# receiver.net
KiCad netlist of a schematic drawn in EAGLE
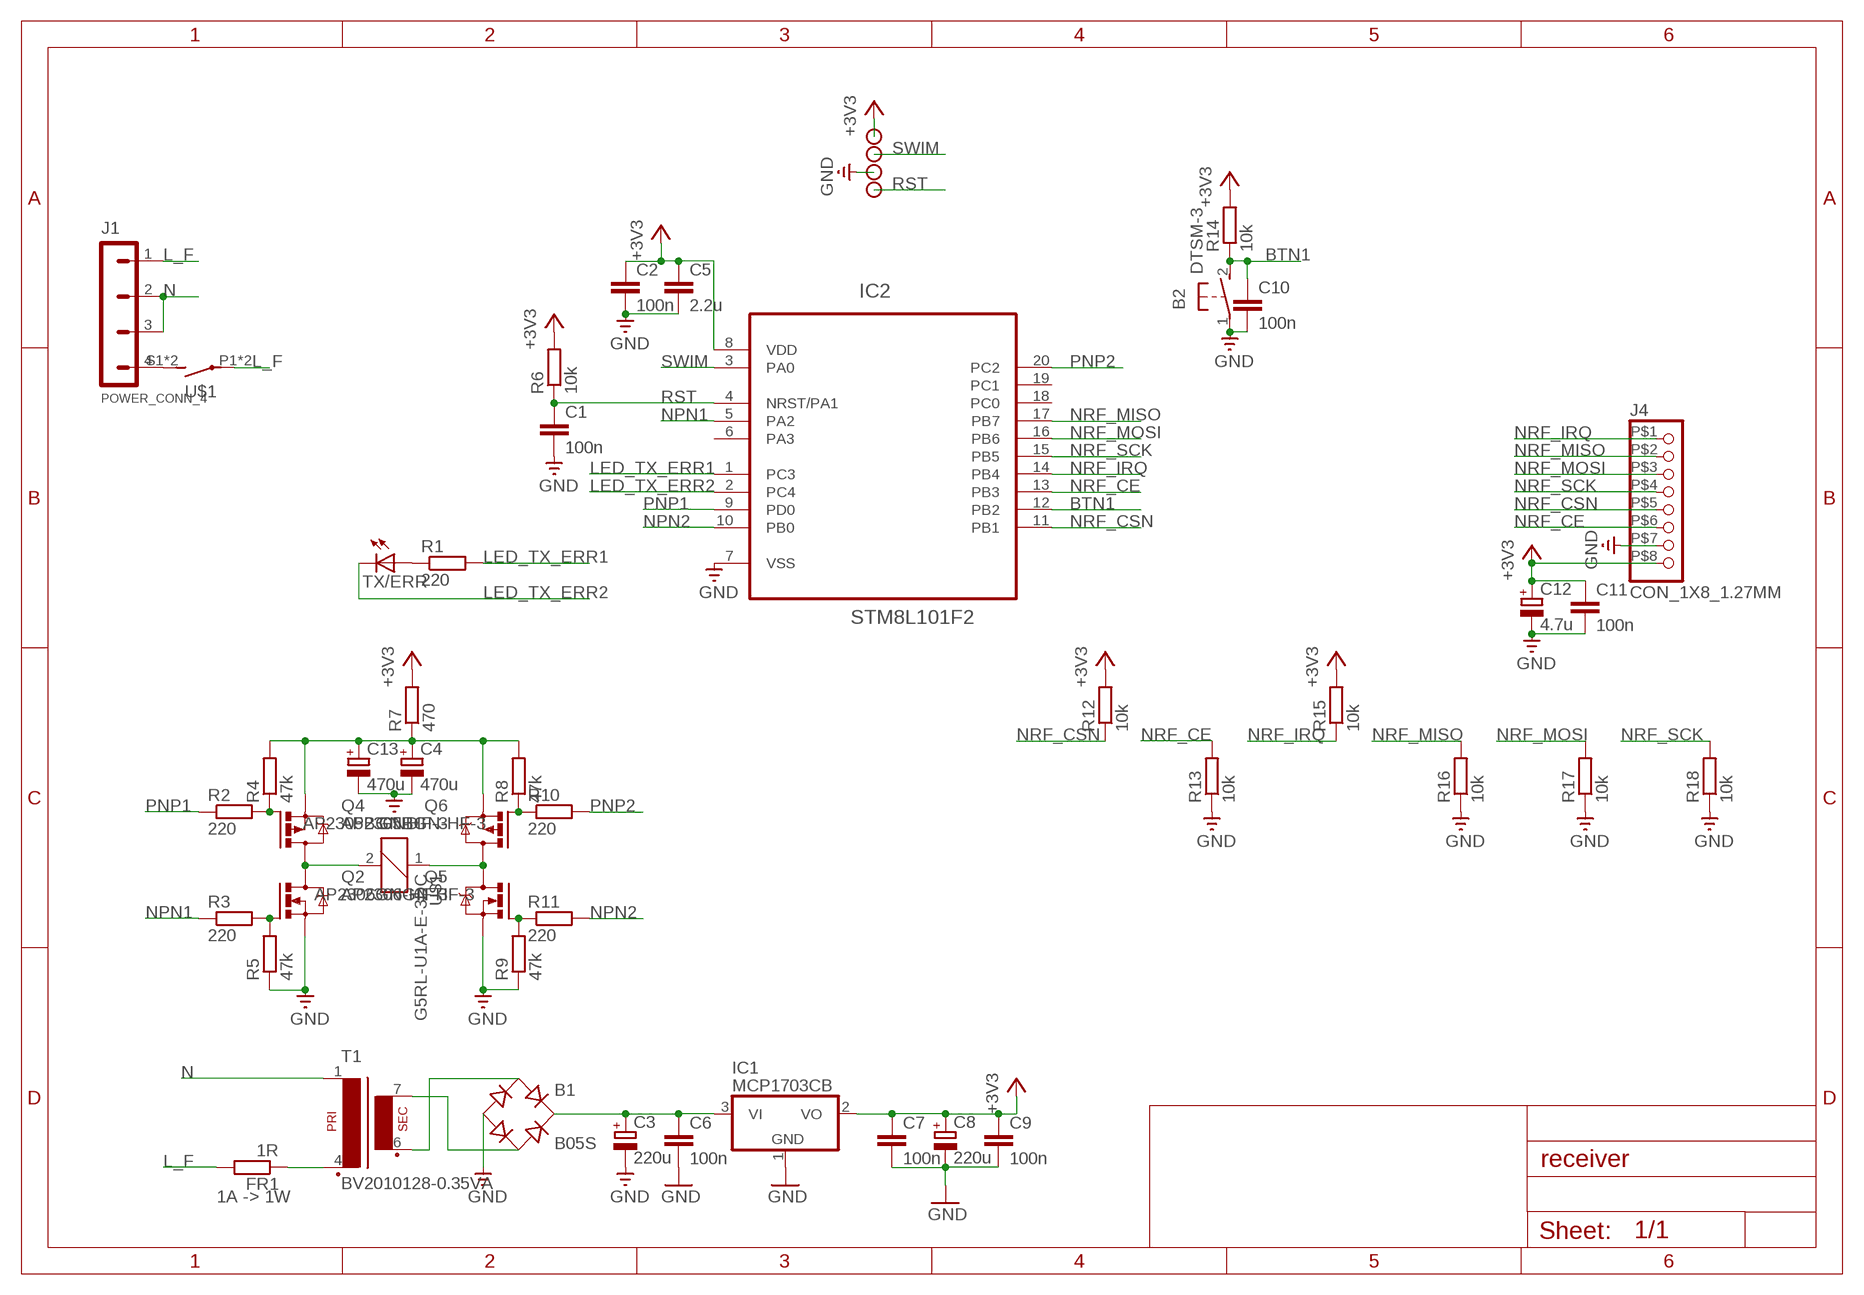
[diagram p0: schematic, sheet 1]

(export (version "E")
  (design (tool "Eeschema 10.0.6"))
  (components
    (comp (ref "B1")
      (value "B05S")
      (footprint "eagle-import:MBS")
      (libsource (lib "eagle-import") (part "BS05"))
    )
    (comp (ref "B2")
      (value "DTSM-3")
      (footprint "eagle-import:DTSM-3")
      (libsource (lib "eagle-import") (part "DTSM-3"))
    )
    (comp (ref "C1")
      (value "100n")
      (footprint "eagle-import:C0603K")
      (libsource (lib "eagle-import") (part "C-EUC0603K"))
    )
    (comp (ref "C2")
      (value "100n")
      (footprint "eagle-import:C0603K")
      (libsource (lib "eagle-import") (part "C-EUC0603K"))
    )
    (comp (ref "C3")
      (value "220u")
      (footprint "eagle-import:E3,5-8")
      (libsource (lib "eagle-import") (part "CPOL-EUE3.5-8"))
    )
    (comp (ref "C4")
      (value "470u")
      (footprint "eagle-import:E2,5-6")
      (libsource (lib "eagle-import") (part "CPOL-EUE2.5-6"))
    )
    (comp (ref "C5")
      (value "2.2u")
      (footprint "eagle-import:C0805K")
      (libsource (lib "eagle-import") (part "C-EUC0805K"))
    )
    (comp (ref "C6")
      (value "100n")
      (footprint "eagle-import:C0603K")
      (libsource (lib "eagle-import") (part "C-EUC0603K"))
    )
    (comp (ref "C7")
      (value "100n")
      (footprint "eagle-import:C0603K")
      (libsource (lib "eagle-import") (part "C-EUC0603K"))
    )
    (comp (ref "C8")
      (value "220u")
      (footprint "eagle-import:E2,5-6")
      (libsource (lib "eagle-import") (part "CPOL-EUE2.5-6"))
    )
    (comp (ref "C9")
      (value "100n")
      (footprint "eagle-import:C0603K")
      (libsource (lib "eagle-import") (part "C-EUC0603K"))
    )
    (comp (ref "C10")
      (value "100n")
      (footprint "eagle-import:C0603K")
      (libsource (lib "eagle-import") (part "C-EUC0603K"))
    )
    (comp (ref "C11")
      (value "100n")
      (footprint "eagle-import:C0603K")
      (libsource (lib "eagle-import") (part "C-EUC0603K"))
    )
    (comp (ref "C12")
      (value "4.7u")
      (footprint "eagle-import:SMC_A")
      (libsource (lib "eagle-import") (part "CPOL-EUSMCA"))
    )
    (comp (ref "C13")
      (value "470u")
      (footprint "eagle-import:E2,5-6")
      (libsource (lib "eagle-import") (part "CPOL-EUE2.5-6"))
    )
    (comp (ref "FR1")
      (value "1R")
      (footprint "eagle-import:0309_10")
      (libsource (lib "eagle-import") (part "R-EU_0309/10"))
    )
    (comp (ref "IC1")
      (value "MCP1703CB")
      (footprint "eagle-import:SOT23")
      (libsource (lib "eagle-import") (part "MCP1703CB"))
    )
    (comp (ref "IC2")
      (value "STM8L101F2")
      (footprint "eagle-import:TSSOP20")
      (libsource (lib "eagle-import") (part "STM8L101F2"))
    )
    (comp (ref "J1")
      (value "POWER_CONN_4")
      (footprint "eagle-import:TERMINAL_BLOCK_4")
      (libsource (lib "eagle-import") (part "POWER_CONN_4"))
    )
    (comp (ref "J4")
      (value "CON_1X8_1.27MM")
      (footprint "eagle-import:CON_1X8PIN_1.27MM")
      (libsource (lib "eagle-import") (part "CON_1X8_1.27MM"))
    )
    (comp (ref "Q2")
      (value "AP2306GN-HF-3")
      (footprint "eagle-import:SOT23")
      (libsource (lib "eagle-import") (part "AP2306GN-HF-3"))
    )
    (comp (ref "Q4")
      (value "AP2305BGN-HF-3")
      (footprint "eagle-import:SOT23")
      (libsource (lib "eagle-import") (part "AP2305BGN-HF-3"))
    )
    (comp (ref "Q5")
      (value "AP2306GN-HF-3")
      (footprint "eagle-import:SOT23")
      (libsource (lib "eagle-import") (part "AP2306GN-HF-3"))
    )
    (comp (ref "Q6")
      (value "AP2305BGN-HF-3")
      (footprint "eagle-import:SOT23")
      (libsource (lib "eagle-import") (part "AP2305BGN-HF-3"))
    )
    (comp (ref "R1")
      (value "220")
      (footprint "eagle-import:R0603")
      (libsource (lib "eagle-import") (part "R-EU_R0603"))
    )
    (comp (ref "R2")
      (value "220")
      (footprint "eagle-import:R0603")
      (libsource (lib "eagle-import") (part "R-EU_R0603"))
    )
    (comp (ref "R3")
      (value "220")
      (footprint "eagle-import:R0603")
      (libsource (lib "eagle-import") (part "R-EU_R0603"))
    )
    (comp (ref "R4")
      (value "47k")
      (footprint "eagle-import:R0603")
      (libsource (lib "eagle-import") (part "R-EU_R0603"))
    )
    (comp (ref "R5")
      (value "47k")
      (footprint "eagle-import:R0603")
      (libsource (lib "eagle-import") (part "R-EU_R0603"))
    )
    (comp (ref "R6")
      (value "10k")
      (footprint "eagle-import:R0603")
      (libsource (lib "eagle-import") (part "R-EU_R0603"))
    )
    (comp (ref "R7")
      (value "470")
      (footprint "eagle-import:R0603")
      (libsource (lib "eagle-import") (part "R-EU_R0603"))
    )
    (comp (ref "R8")
      (value "47k")
      (footprint "eagle-import:R0603")
      (libsource (lib "eagle-import") (part "R-EU_R0603"))
    )
    (comp (ref "R9")
      (value "47k")
      (footprint "eagle-import:R0603")
      (libsource (lib "eagle-import") (part "R-EU_R0603"))
    )
    (comp (ref "R10")
      (value "220")
      (footprint "eagle-import:R0603")
      (libsource (lib "eagle-import") (part "R-EU_R0603"))
    )
    (comp (ref "R11")
      (value "220")
      (footprint "eagle-import:R0603")
      (libsource (lib "eagle-import") (part "R-EU_R0603"))
    )
    (comp (ref "R12")
      (value "10k")
      (footprint "eagle-import:R0603")
      (libsource (lib "eagle-import") (part "R-EU_R0603"))
    )
    (comp (ref "R13")
      (value "10k")
      (footprint "eagle-import:R0603")
      (libsource (lib "eagle-import") (part "R-EU_R0603"))
    )
    (comp (ref "R14")
      (value "10k")
      (footprint "eagle-import:R0603")
      (libsource (lib "eagle-import") (part "R-EU_R0603"))
    )
    (comp (ref "R15")
      (value "10k")
      (footprint "eagle-import:R0603")
      (libsource (lib "eagle-import") (part "R-EU_R0603"))
    )
    (comp (ref "R16")
      (value "10k")
      (footprint "eagle-import:R0603")
      (libsource (lib "eagle-import") (part "R-EU_R0603"))
    )
    (comp (ref "R17")
      (value "10k")
      (footprint "eagle-import:R0603")
      (libsource (lib "eagle-import") (part "R-EU_R0603"))
    )
    (comp (ref "R18")
      (value "10k")
      (footprint "eagle-import:R0603")
      (libsource (lib "eagle-import") (part "R-EU_R0603"))
    )
    (comp (ref "SIG_+3V1")
      (value "CON_PAD")
      (footprint "eagle-import:SMD_PAD")
      (libsource (lib "eagle-import") (part "CON_PAD"))
    )
    (comp (ref "SIG_GND")
      (value "CON_PAD")
      (footprint "eagle-import:SMD_PAD")
      (libsource (lib "eagle-import") (part "CON_PAD"))
    )
    (comp (ref "SIG_RST")
      (value "CON_PAD")
      (footprint "eagle-import:SMD_PAD")
      (libsource (lib "eagle-import") (part "CON_PAD"))
    )
    (comp (ref "SIG_SWIM")
      (value "CON_PAD")
      (footprint "eagle-import:SMD_PAD")
      (libsource (lib "eagle-import") (part "CON_PAD"))
    )
    (comp (ref "T1")
      (value "BV2010128-0.35VA")
      (footprint "eagle-import:BV2010128-0.35VA")
      (libsource (lib "eagle-import") (part "BV2010128-0.35VA"))
    )
    (comp (ref "TX/ERR")
      (value "LED3MM")
      (footprint "eagle-import:LED3MM")
      (libsource (lib "eagle-import") (part "LED3MM"))
    )
    (comp (ref "U$1")
      (value "G5RL-U1A-E-3DC")
      (footprint "eagle-import:G5RL-U1A-E-3DC")
      (libsource (lib "eagle-import") (part "G5RL-U1A-E-3DC"))
    )
  )
  (nets
    (net (code "1") (name "+3V3") (class "Default")
      (node (ref "C11") (pin "1") (pinfunction "1_1") (pintype "passive"))
      (node (ref "C12") (pin "+") (pinfunction "+_+") (pintype "passive"))
      (node (ref "C2") (pin "1") (pinfunction "1_1") (pintype "passive"))
      (node (ref "C5") (pin "1") (pinfunction "1_1") (pintype "passive"))
      (node (ref "C7") (pin "1") (pinfunction "1_1") (pintype "passive"))
      (node (ref "C8") (pin "+") (pinfunction "+_+") (pintype "passive"))
      (node (ref "C9") (pin "1") (pinfunction "1_1") (pintype "passive"))
      (node (ref "IC1") (pin "2") (pinfunction "VO_2") (pintype "passive"))
      (node (ref "IC2") (pin "8") (pinfunction "VDD_8") (pintype "power_in"))
      (node (ref "J4") (pin "P$8") (pinfunction "8_P$8") (pintype "passive"))
      (node (ref "R12") (pin "2") (pinfunction "2_2") (pintype "passive"))
      (node (ref "R14") (pin "2") (pinfunction "2_2") (pintype "passive"))
      (node (ref "R15") (pin "2") (pinfunction "2_2") (pintype "passive"))
      (node (ref "R6") (pin "2") (pinfunction "2_2") (pintype "passive"))
      (node (ref "R7") (pin "2") (pinfunction "2_2") (pintype "passive"))
      (node (ref "SIG_+3V1") (pin "P$1") (pinfunction "P$1_P$1") (pintype "bidirectional"))
    )
    (net (code "2") (name "/BTN1") (class "Default")
      (node (ref "B2") (pin "2") (pinfunction "2_2") (pintype "passive"))
      (node (ref "C10") (pin "1") (pinfunction "1_1") (pintype "passive"))
      (node (ref "IC2") (pin "12") (pinfunction "PB2_12") (pintype "bidirectional"))
      (node (ref "R14") (pin "1") (pinfunction "1_1") (pintype "passive"))
    )
    (net (code "3") (name "/LED_TX_ERR1") (class "Default")
      (node (ref "IC2") (pin "1") (pinfunction "PC3_1") (pintype "bidirectional"))
      (node (ref "R1") (pin "2") (pinfunction "2_2") (pintype "passive"))
    )
    (net (code "4") (name "/LED_TX_ERR2") (class "Default")
      (node (ref "IC2") (pin "2") (pinfunction "PC4_2") (pintype "bidirectional"))
      (node (ref "TX/ERR") (pin "K") (pinfunction "C_K") (pintype "passive"))
    )
    (net (code "5") (name "/L_F") (class "Default")
      (node (ref "FR1") (pin "2") (pinfunction "2_2") (pintype "passive"))
      (node (ref "J1") (pin "1") (pinfunction "P$1_1") (pintype "bidirectional"))
      (node (ref "U$1") (pin "P1") (pinfunction "P_P1") (pintype "passive"))
      (node (ref "U$1") (pin "P2") (pinfunction "P_P2") (pintype "passive"))
    )
    (net (code "6") (name "/N") (class "Default")
      (node (ref "J1") (pin "2") (pinfunction "P$2_2") (pintype "bidirectional"))
      (node (ref "J1") (pin "3") (pinfunction "P$3_3") (pintype "bidirectional"))
      (node (ref "T1") (pin "1") (pinfunction "P1_1") (pintype "passive"))
    )
    (net (code "7") (name "/NPN1") (class "Default")
      (node (ref "IC2") (pin "5") (pinfunction "PA2_5") (pintype "bidirectional"))
      (node (ref "R3") (pin "1") (pinfunction "1_1") (pintype "passive"))
    )
    (net (code "8") (name "/NPN2") (class "Default")
      (node (ref "IC2") (pin "10") (pinfunction "PB0_10") (pintype "bidirectional"))
      (node (ref "R11") (pin "2") (pinfunction "2_2") (pintype "passive"))
    )
    (net (code "9") (name "/NRF_CE") (class "Default")
      (node (ref "IC2") (pin "13") (pinfunction "PB3_13") (pintype "bidirectional"))
      (node (ref "J4") (pin "P$6") (pinfunction "6_P$6") (pintype "passive"))
      (node (ref "R13") (pin "2") (pinfunction "2_2") (pintype "passive"))
    )
    (net (code "10") (name "/NRF_CSN") (class "Default")
      (node (ref "IC2") (pin "11") (pinfunction "PB1_11") (pintype "bidirectional"))
      (node (ref "J4") (pin "P$5") (pinfunction "5_P$5") (pintype "passive"))
      (node (ref "R12") (pin "1") (pinfunction "1_1") (pintype "passive"))
    )
    (net (code "11") (name "/NRF_IRQ") (class "Default")
      (node (ref "IC2") (pin "14") (pinfunction "PB4_14") (pintype "bidirectional"))
      (node (ref "J4") (pin "P$1") (pinfunction "1_P$1") (pintype "passive"))
      (node (ref "R15") (pin "1") (pinfunction "1_1") (pintype "passive"))
    )
    (net (code "12") (name "/NRF_MISO") (class "Default")
      (node (ref "IC2") (pin "17") (pinfunction "PB7_17") (pintype "bidirectional"))
      (node (ref "J4") (pin "P$2") (pinfunction "2_P$2") (pintype "passive"))
      (node (ref "R16") (pin "2") (pinfunction "2_2") (pintype "passive"))
    )
    (net (code "13") (name "/NRF_MOSI") (class "Default")
      (node (ref "IC2") (pin "16") (pinfunction "PB6_16") (pintype "bidirectional"))
      (node (ref "J4") (pin "P$3") (pinfunction "3_P$3") (pintype "passive"))
      (node (ref "R17") (pin "2") (pinfunction "2_2") (pintype "passive"))
    )
    (net (code "14") (name "/NRF_SCK") (class "Default")
      (node (ref "IC2") (pin "15") (pinfunction "PB5_15") (pintype "bidirectional"))
      (node (ref "J4") (pin "P$4") (pinfunction "4_P$4") (pintype "passive"))
      (node (ref "R18") (pin "2") (pinfunction "2_2") (pintype "passive"))
    )
    (net (code "15") (name "/PNP1") (class "Default")
      (node (ref "IC2") (pin "9") (pinfunction "PD0_9") (pintype "bidirectional"))
      (node (ref "R2") (pin "1") (pinfunction "1_1") (pintype "passive"))
    )
    (net (code "16") (name "/PNP2") (class "Default")
      (node (ref "IC2") (pin "20") (pinfunction "PC2_20") (pintype "bidirectional"))
      (node (ref "R10") (pin "2") (pinfunction "2_2") (pintype "passive"))
    )
    (net (code "17") (name "/RST") (class "Default")
      (node (ref "C1") (pin "1") (pinfunction "1_1") (pintype "passive"))
      (node (ref "IC2") (pin "4") (pinfunction "NRST/PA1_4") (pintype "bidirectional"))
      (node (ref "R6") (pin "1") (pinfunction "1_1") (pintype "passive"))
      (node (ref "SIG_RST") (pin "P$1") (pinfunction "P$1_P$1") (pintype "bidirectional"))
    )
    (net (code "18") (name "/SWIM") (class "Default")
      (node (ref "IC2") (pin "3") (pinfunction "PA0_3") (pintype "power_in"))
      (node (ref "SIG_SWIM") (pin "P$1") (pinfunction "P$1_P$1") (pintype "bidirectional"))
    )
    (net (code "19") (name "GND") (class "Default")
      (node (ref "B1") (pin "-") (pinfunction "-_-") (pintype "passive"))
      (node (ref "B2") (pin "1") (pinfunction "1_1") (pintype "passive"))
      (node (ref "C1") (pin "2") (pinfunction "2_2") (pintype "passive"))
      (node (ref "C10") (pin "2") (pinfunction "2_2") (pintype "passive"))
      (node (ref "C11") (pin "2") (pinfunction "2_2") (pintype "passive"))
      (node (ref "C12") (pin "-") (pinfunction "-_-") (pintype "passive"))
      (node (ref "C13") (pin "-") (pinfunction "-_-") (pintype "passive"))
      (node (ref "C2") (pin "2") (pinfunction "2_2") (pintype "passive"))
      (node (ref "C3") (pin "-") (pinfunction "-_-") (pintype "passive"))
      (node (ref "C4") (pin "-") (pinfunction "-_-") (pintype "passive"))
      (node (ref "C5") (pin "2") (pinfunction "2_2") (pintype "passive"))
      (node (ref "C6") (pin "2") (pinfunction "2_2") (pintype "passive"))
      (node (ref "C7") (pin "2") (pinfunction "2_2") (pintype "passive"))
      (node (ref "C8") (pin "-") (pinfunction "-_-") (pintype "passive"))
      (node (ref "C9") (pin "2") (pinfunction "2_2") (pintype "passive"))
      (node (ref "IC1") (pin "1") (pinfunction "GND_1") (pintype "passive"))
      (node (ref "IC2") (pin "7") (pinfunction "VSS_7") (pintype "power_in"))
      (node (ref "J4") (pin "P$7") (pinfunction "7_P$7") (pintype "passive"))
      (node (ref "Q2") (pin "2") (pinfunction "S_2") (pintype "passive"))
      (node (ref "Q5") (pin "2") (pinfunction "S_2") (pintype "passive"))
      (node (ref "R13") (pin "1") (pinfunction "1_1") (pintype "passive"))
      (node (ref "R16") (pin "1") (pinfunction "1_1") (pintype "passive"))
      (node (ref "R17") (pin "1") (pinfunction "1_1") (pintype "passive"))
      (node (ref "R18") (pin "1") (pinfunction "1_1") (pintype "passive"))
      (node (ref "R5") (pin "1") (pinfunction "1_1") (pintype "passive"))
      (node (ref "R9") (pin "1") (pinfunction "1_1") (pintype "passive"))
      (node (ref "SIG_GND") (pin "P$1") (pinfunction "P$1_P$1") (pintype "bidirectional"))
    )
    (net (code "20") (name "Net-(IC1-VI)") (class "Default")
      (node (ref "B1") (pin "+") (pinfunction "+_+") (pintype "passive"))
      (node (ref "C3") (pin "+") (pinfunction "+_+") (pintype "passive"))
      (node (ref "C6") (pin "1") (pinfunction "1_1") (pintype "passive"))
      (node (ref "IC1") (pin "3") (pinfunction "VI_3") (pintype "input"))
    )
    (net (code "21") (name "Net-(J1-P$4)") (class "Default")
      (node (ref "J1") (pin "4") (pinfunction "P$4_4") (pintype "bidirectional"))
      (node (ref "U$1") (pin "S1") (pinfunction "S_S1") (pintype "passive"))
      (node (ref "U$1") (pin "S2") (pinfunction "S_S2") (pintype "passive"))
    )
    (net (code "22") (name "Net-(Q2-D)") (class "Default")
      (node (ref "Q2") (pin "3") (pinfunction "D_3") (pintype "passive"))
      (node (ref "Q4") (pin "3") (pinfunction "D_3") (pintype "passive"))
      (node (ref "U$1") (pin "2") (pinfunction "2_2") (pintype "passive"))
    )
    (net (code "23") (name "Net-(Q2-G)") (class "Default")
      (node (ref "Q2") (pin "1") (pinfunction "G_1") (pintype "passive"))
      (node (ref "R3") (pin "2") (pinfunction "2_2") (pintype "passive"))
      (node (ref "R5") (pin "2") (pinfunction "2_2") (pintype "passive"))
    )
    (net (code "24") (name "Net-(Q4-G)") (class "Default")
      (node (ref "Q4") (pin "1") (pinfunction "G_1") (pintype "passive"))
      (node (ref "R2") (pin "2") (pinfunction "2_2") (pintype "passive"))
      (node (ref "R4") (pin "1") (pinfunction "1_1") (pintype "passive"))
    )
    (net (code "25") (name "Net-(Q4-S)") (class "Default")
      (node (ref "C13") (pin "+") (pinfunction "+_+") (pintype "passive"))
      (node (ref "C4") (pin "+") (pinfunction "+_+") (pintype "passive"))
      (node (ref "Q4") (pin "2") (pinfunction "S_2") (pintype "passive"))
      (node (ref "Q6") (pin "2") (pinfunction "S_2") (pintype "passive"))
      (node (ref "R4") (pin "2") (pinfunction "2_2") (pintype "passive"))
      (node (ref "R7") (pin "1") (pinfunction "1_1") (pintype "passive"))
      (node (ref "R8") (pin "2") (pinfunction "2_2") (pintype "passive"))
    )
    (net (code "26") (name "Net-(Q5-D)") (class "Default")
      (node (ref "Q5") (pin "3") (pinfunction "D_3") (pintype "passive"))
      (node (ref "Q6") (pin "3") (pinfunction "D_3") (pintype "passive"))
      (node (ref "U$1") (pin "1") (pinfunction "1_1") (pintype "passive"))
    )
    (net (code "27") (name "Net-(Q5-G)") (class "Default")
      (node (ref "Q5") (pin "1") (pinfunction "G_1") (pintype "passive"))
      (node (ref "R11") (pin "1") (pinfunction "1_1") (pintype "passive"))
      (node (ref "R9") (pin "2") (pinfunction "2_2") (pintype "passive"))
    )
    (net (code "28") (name "Net-(Q6-G)") (class "Default")
      (node (ref "Q6") (pin "1") (pinfunction "G_1") (pintype "passive"))
      (node (ref "R10") (pin "1") (pinfunction "1_1") (pintype "passive"))
      (node (ref "R8") (pin "1") (pinfunction "1_1") (pintype "passive"))
    )
    (net (code "29") (name "Net-(R1-Pad1)") (class "Default")
      (node (ref "R1") (pin "1") (pinfunction "1_1") (pintype "passive"))
      (node (ref "TX/ERR") (pin "A") (pinfunction "A_A") (pintype "passive"))
    )
    (net (code "30") (name "Net-(T1-P2)") (class "Default")
      (node (ref "FR1") (pin "1") (pinfunction "1_1") (pintype "passive"))
      (node (ref "T1") (pin "4") (pinfunction "P2_4") (pintype "passive"))
    )
    (net (code "31") (name "Net-(T1-S3)") (class "Default")
      (node (ref "B1") (pin "AC1") (pinfunction "AC1_AC1") (pintype "passive"))
      (node (ref "T1") (pin "6") (pinfunction "S3_6") (pintype "passive"))
    )
    (net (code "32") (name "Net-(T1-S4)") (class "Default")
      (node (ref "B1") (pin "AC2") (pinfunction "AC2_AC2") (pintype "passive"))
      (node (ref "T1") (pin "7") (pinfunction "S4_7") (pintype "passive"))
    )
    (net (code "33") (name "unconnected-(IC2-PA3-Pad6)") (class "Default")
      (node (ref "IC2") (pin "6") (pinfunction "PA3_6") (pintype "bidirectional"))
    )
    (net (code "34") (name "unconnected-(IC2-PC0-Pad18)") (class "Default")
      (node (ref "IC2") (pin "18") (pinfunction "PC0_18") (pintype "bidirectional"))
    )
    (net (code "35") (name "unconnected-(IC2-PC1-Pad19)") (class "Default")
      (node (ref "IC2") (pin "19") (pinfunction "PC1_19") (pintype "bidirectional"))
    )
  )
)
